# piezo_flasher_v2_0.net
KiCad netlist of a schematic drawn in EAGLE
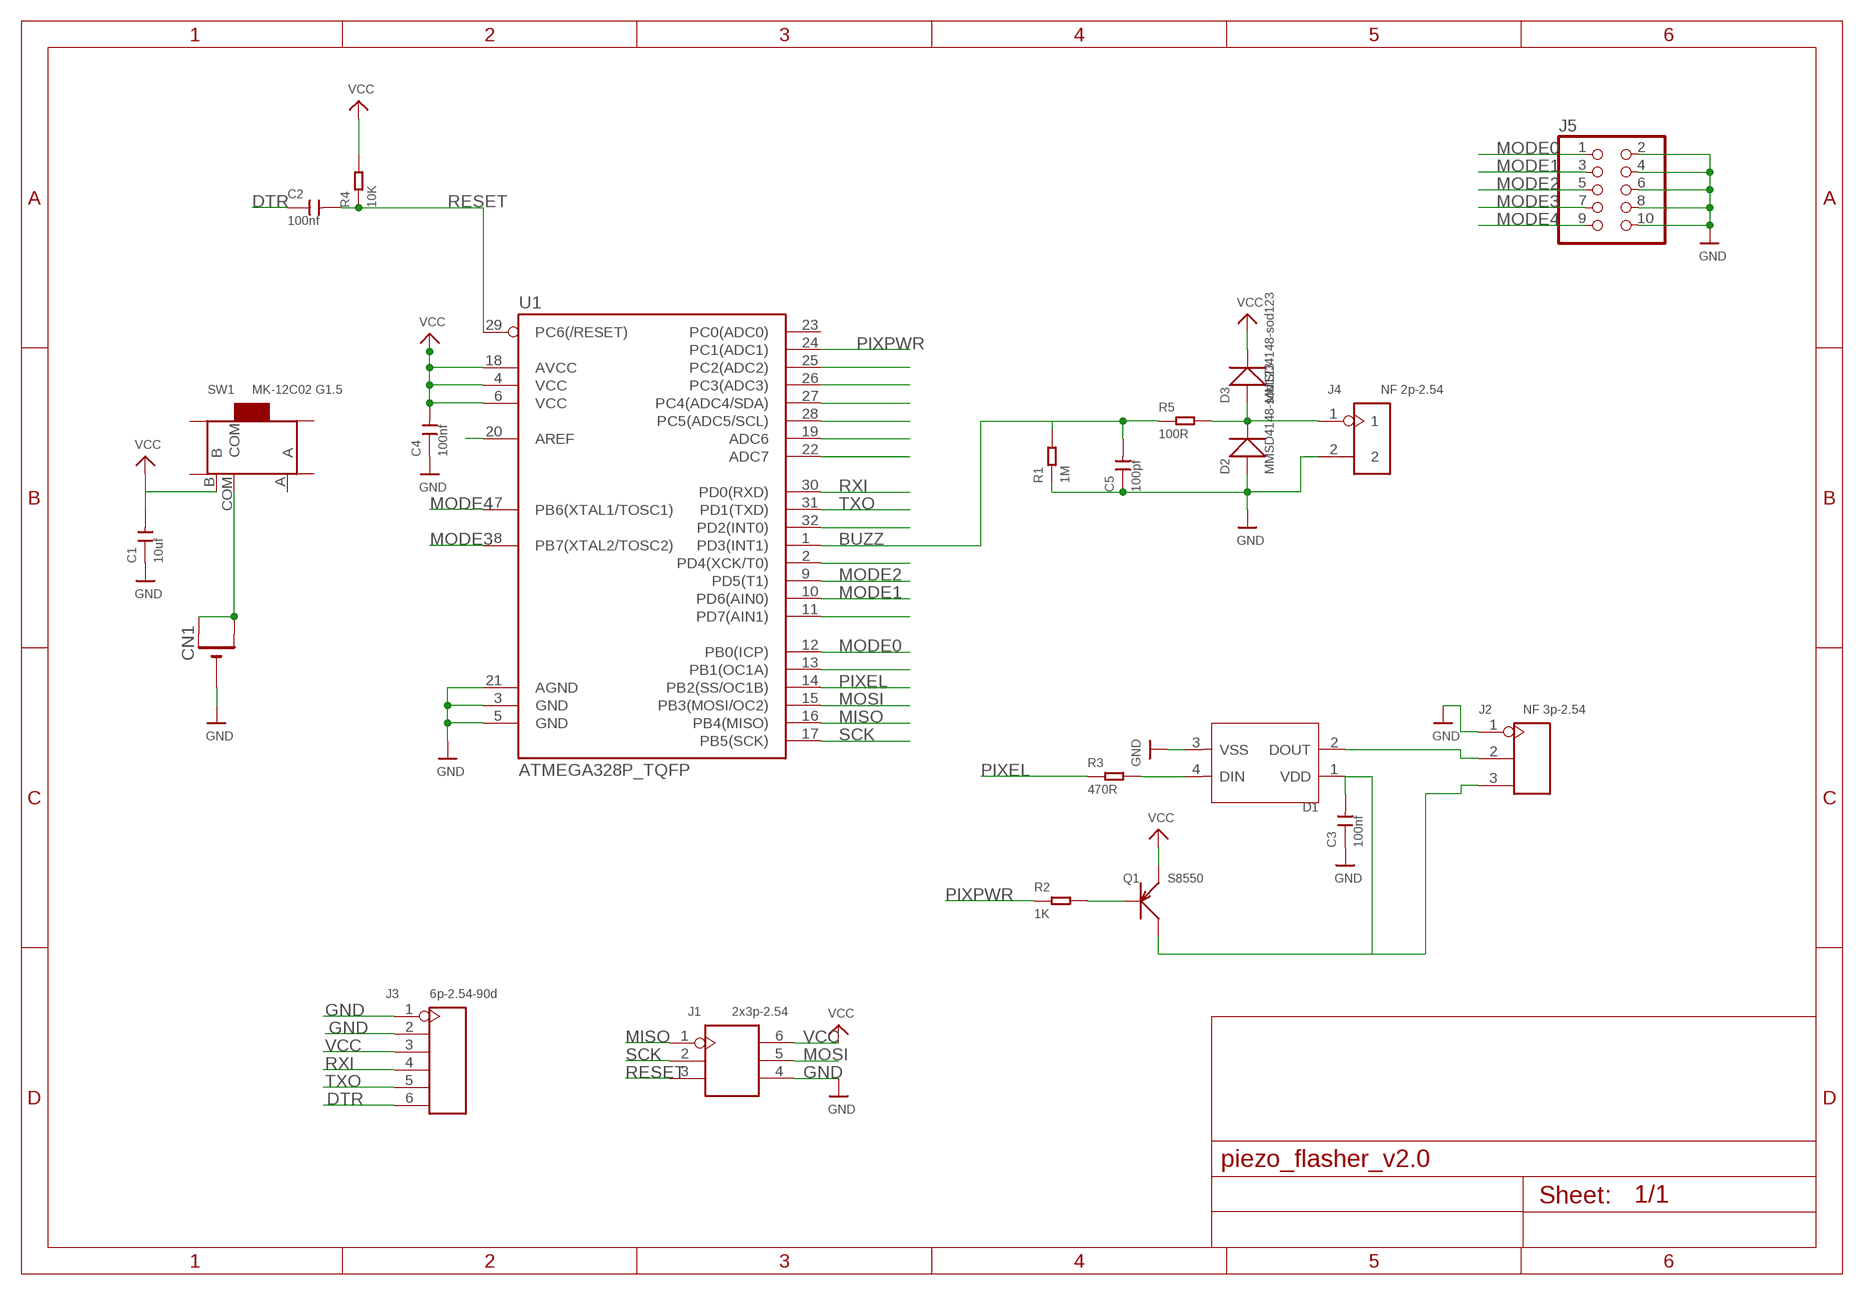
[diagram p0: schematic, sheet 1]

(export (version "E")
  (design (tool "Eeschema 10.0.6"))
  (components
    (comp (ref "C1")
      (value "10uf")
      (footprint "eagle-import:C0805")
      (fields (field (name "MPN") "CC0805KKX5R8BB106"))
      (libsource (lib "eagle-import") (part "CERAMIC-10UF-25V-10%-X5R(0805)"))
    )
    (comp (ref "C2")
      (value "100nf")
      (footprint "eagle-import:C0805")
      (fields (field (name "MPN") "CC0805KRX7R9BB104"))
      (libsource (lib "eagle-import") (part "CERAMIC-100NF-50V-10%-X7R(0805)"))
    )
    (comp (ref "C3")
      (value "100nf")
      (footprint "eagle-import:C0805")
      (fields (field (name "MPN") "CC0805KRX7R9BB104"))
      (libsource (lib "eagle-import") (part "CERAMIC-100NF-50V-10%-X7R(0805)"))
    )
    (comp (ref "C4")
      (value "100nf")
      (footprint "eagle-import:C0805")
      (fields (field (name "MPN") "CC0805KRX7R9BB104"))
      (libsource (lib "eagle-import") (part "CERAMIC-100NF-50V-10%-X7R(0805)"))
    )
    (comp (ref "C5")
      (value "100pf")
      (footprint "eagle-import:C0603")
      (fields (field (name "MPN") "CC0603JRNPO9BN101"))
      (libsource (lib "eagle-import") (part "CERAMIC-100PF-50V-5%-NPO(0603)"))
    )
    (comp (ref "CN1")
      (value "CR2032SMT")
      (footprint "eagle-import:CR2032-SMD")
      (libsource (lib "eagle-import") (part "CR2032SMT"))
    )
    (comp (ref "D1")
      (value "SMD-RGB-LED-4P'WS2812B'")
      (footprint "eagle-import:LED4-SMD-5050")
      (libsource (lib "eagle-import") (part "SMD-RGB-LED-4P'WS2812B'"))
    )
    (comp (ref "D2")
      (value "MMSD4148-sod123")
      (footprint "eagle-import:SOD-123")
      (fields (field (name "MPN") "MMSD4148"))
      (libsource (lib "eagle-import") (part "SMD-DIODE-100V-200MA(SOD-123)"))
    )
    (comp (ref "D3")
      (value "MMSD4148-sod123")
      (footprint "eagle-import:SOD-123")
      (fields (field (name "MPN") "MMSD4148"))
      (libsource (lib "eagle-import") (part "SMD-DIODE-100V-200MA(SOD-123)"))
    )
    (comp (ref "J1")
      (value "2x3p-2.54")
      (footprint "eagle-import:H2X3-2.54")
      (fields (field (name "MPN") "P125-12A1BS116A1"))
      (libsource (lib "eagle-import") (part "DIP-BLACK-MALE-HEADER(2X3P-2.54）-2.54"))
    )
    (comp (ref "J2")
      (value "NF 3p-2.54")
      (footprint "eagle-import:H3-2.54")
      (libsource (lib "eagle-import") (part "DIP-BLACK-MALE-HEADER-VERT(3P-2.54)"))
    )
    (comp (ref "J3")
      (value "6p-2.54-90d")
      (footprint "eagle-import:H6-2.54-90D-MALE")
      (libsource (lib "eagle-import") (part "DIP-BLACK-SHORT-MALE-HEADER-R/A(6P-2.54-90D)"))
    )
    (comp (ref "J4")
      (value "NF 2p-2.54")
      (footprint "eagle-import:H2-2.54")
      (fields (field (name "MPN") "P125-1102A0BS116A1"))
      (libsource (lib "eagle-import") (part "DIP-BLACK-MALE-HEADER-VERT(2P-2.54)"))
    )
    (comp (ref "J5")
      (value "HEADER-2X5")
      (footprint "eagle-import:2X05")
      (libsource (lib "eagle-import") (part "HEADER-2X5"))
    )
    (comp (ref "Q1")
      (value "S8550")
      (footprint "eagle-import:SOT-23")
      (libsource (lib "eagle-import") (part "SMD-TRANSISTORS-PNP-25V-500MA-S8550(SOT-23)"))
    )
    (comp (ref "R1")
      (value "1M")
      (footprint "eagle-import:R0603")
      (fields (field (name "MPN") "RC0603FR-071ML"))
      (libsource (lib "eagle-import") (part "SMD-RES-1M-1%-1/10W(0603)"))
    )
    (comp (ref "R2")
      (value "1K")
      (footprint "eagle-import:R0805")
      (fields (field (name "MPN") "RC0805JR-071KL"))
      (libsource (lib "eagle-import") (part "SMD-RES-1K-5%-1/8W(0805)"))
    )
    (comp (ref "R3")
      (value "470R")
      (footprint "eagle-import:R0603")
      (fields (field (name "MPN") "RC0603JR-07470RL"))
      (libsource (lib "eagle-import") (part "SMD-RES-470R-5%-1/10W(0603)"))
    )
    (comp (ref "R4")
      (value "10K")
      (footprint "eagle-import:R0805")
      (fields (field (name "MPN") "RC0805FR-0710KL"))
      (libsource (lib "eagle-import") (part "SMD-RES-10K-1%-1/8W(0805)"))
    )
    (comp (ref "R5")
      (value "100R")
      (footprint "eagle-import:R0805")
      (fields (field (name "MPN") "RC0805JR-07100RL"))
      (libsource (lib "eagle-import") (part "SMD-RES-100R-5%-1/8W(0805)"))
    )
    (comp (ref "SW1")
      (value "MK-12C02 G1.5")
      (footprint "eagle-import:SW7-SMD-L6.7X2.7X3.2MM")
      (libsource (lib "eagle-import") (part "SMD-TOGGLE-SWITCH-ON-ON(3+4P-6.7X2.7MM)"))
    )
    (comp (ref "U1")
      (value "ATMEGA328P_TQFP")
      (footprint "eagle-import:TQFP32-08")
      (libsource (lib "eagle-import") (part "ATMEGA328P_TQFP"))
    )
  )
  (nets
    (net (code "1") (name "/BUZZ") (class "Default")
      (node (ref "C5") (pin "2") (pinfunction "2_2") (pintype "passive"))
      (node (ref "R1") (pin "2") (pinfunction "2_2") (pintype "passive"))
      (node (ref "R5") (pin "1") (pinfunction "1_1") (pintype "passive"))
      (node (ref "U1") (pin "1") (pinfunction "PD3(INT1)_1") (pintype "bidirectional"))
    )
    (net (code "2") (name "/DTR") (class "Default")
      (node (ref "C2") (pin "1") (pinfunction "1_1") (pintype "passive"))
      (node (ref "J3") (pin "6") (pinfunction "6_6") (pintype "bidirectional"))
    )
    (net (code "3") (name "/MISO") (class "Default")
      (node (ref "J1") (pin "1") (pinfunction "1_1") (pintype "bidirectional"))
      (node (ref "U1") (pin "16") (pinfunction "PB4(MISO)_16") (pintype "bidirectional"))
    )
    (net (code "4") (name "/MODE0") (class "Default")
      (node (ref "J5") (pin "1") (pinfunction "1_1") (pintype "passive"))
      (node (ref "U1") (pin "12") (pinfunction "PB0(ICP)_12") (pintype "bidirectional"))
    )
    (net (code "5") (name "/MODE1") (class "Default")
      (node (ref "J5") (pin "3") (pinfunction "3_3") (pintype "passive"))
      (node (ref "U1") (pin "10") (pinfunction "PD6(AIN0)_10") (pintype "bidirectional"))
    )
    (net (code "6") (name "/MODE2") (class "Default")
      (node (ref "J5") (pin "5") (pinfunction "5_5") (pintype "passive"))
      (node (ref "U1") (pin "9") (pinfunction "PD5(T1)_9") (pintype "bidirectional"))
    )
    (net (code "7") (name "/MODE3") (class "Default")
      (node (ref "J5") (pin "7") (pinfunction "7_7") (pintype "passive"))
      (node (ref "U1") (pin "8") (pinfunction "PB7(XTAL2/TOSC2)_8") (pintype "bidirectional"))
    )
    (net (code "8") (name "/MODE4") (class "Default")
      (node (ref "J5") (pin "9") (pinfunction "9_9") (pintype "passive"))
      (node (ref "U1") (pin "7") (pinfunction "PB6(XTAL1/TOSC1)_7") (pintype "bidirectional"))
    )
    (net (code "9") (name "/MOSI") (class "Default")
      (node (ref "J1") (pin "5") (pinfunction "5_5") (pintype "bidirectional"))
      (node (ref "U1") (pin "15") (pinfunction "PB3(MOSI/OC2)_15") (pintype "bidirectional"))
    )
    (net (code "10") (name "/PIXEL") (class "Default")
      (node (ref "R3") (pin "1") (pinfunction "1_1") (pintype "passive"))
      (node (ref "U1") (pin "14") (pinfunction "PB2(SS/OC1B)_14") (pintype "bidirectional"))
    )
    (net (code "11") (name "/PIXPWR") (class "Default")
      (node (ref "R2") (pin "1") (pinfunction "1_1") (pintype "passive"))
      (node (ref "U1") (pin "24") (pinfunction "PC1(ADC1)_24") (pintype "bidirectional"))
    )
    (net (code "12") (name "/RESET") (class "Default")
      (node (ref "C2") (pin "2") (pinfunction "2_2") (pintype "passive"))
      (node (ref "J1") (pin "3") (pinfunction "3_3") (pintype "bidirectional"))
      (node (ref "R4") (pin "1") (pinfunction "1_1") (pintype "passive"))
      (node (ref "U1") (pin "29") (pinfunction "PC6(/RESET)_29") (pintype "bidirectional"))
    )
    (net (code "13") (name "/RXI") (class "Default")
      (node (ref "J3") (pin "4") (pinfunction "4_4") (pintype "bidirectional"))
      (node (ref "U1") (pin "30") (pinfunction "PD0(RXD)_30") (pintype "bidirectional"))
    )
    (net (code "14") (name "/SCK") (class "Default")
      (node (ref "J1") (pin "2") (pinfunction "2_2") (pintype "bidirectional"))
      (node (ref "U1") (pin "17") (pinfunction "PB5(SCK)_17") (pintype "bidirectional"))
    )
    (net (code "15") (name "/TXO") (class "Default")
      (node (ref "J3") (pin "5") (pinfunction "5_5") (pintype "bidirectional"))
      (node (ref "U1") (pin "31") (pinfunction "PD1(TXD)_31") (pintype "bidirectional"))
    )
    (net (code "16") (name "GND") (class "Default")
      (node (ref "C1") (pin "1") (pinfunction "1_1") (pintype "passive"))
      (node (ref "C3") (pin "1") (pinfunction "1_1") (pintype "passive"))
      (node (ref "C4") (pin "1") (pinfunction "1_1") (pintype "passive"))
      (node (ref "C5") (pin "1") (pinfunction "1_1") (pintype "passive"))
      (node (ref "CN1") (pin "-") (pinfunction "-_-") (pintype "passive"))
      (node (ref "D1") (pin "3") (pinfunction "VSS_3") (pintype "bidirectional"))
      (node (ref "D2") (pin "+") (pinfunction "+_+") (pintype "passive"))
      (node (ref "J1") (pin "4") (pinfunction "4_4") (pintype "bidirectional"))
      (node (ref "J2") (pin "1") (pinfunction "P$1_1") (pintype "bidirectional"))
      (node (ref "J3") (pin "1") (pinfunction "1_1") (pintype "bidirectional"))
      (node (ref "J3") (pin "2") (pinfunction "2_2") (pintype "bidirectional"))
      (node (ref "J4") (pin "2") (pinfunction "2_2") (pintype "bidirectional"))
      (node (ref "J5") (pin "10") (pinfunction "10_10") (pintype "passive"))
      (node (ref "J5") (pin "2") (pinfunction "2_2") (pintype "passive"))
      (node (ref "J5") (pin "4") (pinfunction "4_4") (pintype "passive"))
      (node (ref "J5") (pin "6") (pinfunction "6_6") (pintype "passive"))
      (node (ref "J5") (pin "8") (pinfunction "8_8") (pintype "passive"))
      (node (ref "R1") (pin "1") (pinfunction "1_1") (pintype "passive"))
      (node (ref "U1") (pin "21") (pinfunction "AGND_21") (pintype "bidirectional"))
      (node (ref "U1") (pin "3") (pinfunction "GND_3") (pintype "bidirectional"))
      (node (ref "U1") (pin "5") (pinfunction "GND_5") (pintype "bidirectional"))
    )
    (net (code "17") (name "Net-(CN1-+)") (class "Default")
      (node (ref "CN1") (pin "+$1") (pinfunction "+_+$1") (pintype "passive"))
      (node (ref "CN1") (pin "+$2") (pinfunction "+1_+$2") (pintype "passive"))
      (node (ref "SW1") (pin "COM") (pinfunction "COM_COM") (pintype "bidirectional"))
    )
    (net (code "18") (name "Net-(D1-DIN)") (class "Default")
      (node (ref "D1") (pin "4") (pinfunction "DIN_4") (pintype "bidirectional"))
      (node (ref "R3") (pin "2") (pinfunction "2_2") (pintype "passive"))
    )
    (net (code "19") (name "Net-(D1-DOUT)") (class "Default")
      (node (ref "D1") (pin "2") (pinfunction "DOUT_2") (pintype "bidirectional"))
      (node (ref "J2") (pin "2") (pinfunction "P$2_2") (pintype "bidirectional"))
    )
    (net (code "20") (name "Net-(D1-VDD)") (class "Default")
      (node (ref "C3") (pin "2") (pinfunction "2_2") (pintype "passive"))
      (node (ref "D1") (pin "1") (pinfunction "VDD_1") (pintype "bidirectional"))
      (node (ref "J2") (pin "3") (pinfunction "P$3_3") (pintype "bidirectional"))
      (node (ref "Q1") (pin "3") (pinfunction "C_3") (pintype "passive"))
    )
    (net (code "21") (name "Net-(D2-Pad-)") (class "Default")
      (node (ref "D2") (pin "-") (pinfunction "-_-") (pintype "passive"))
      (node (ref "D3") (pin "+") (pinfunction "+_+") (pintype "passive"))
      (node (ref "J4") (pin "1") (pinfunction "1_1") (pintype "bidirectional"))
      (node (ref "R5") (pin "2") (pinfunction "2_2") (pintype "passive"))
    )
    (net (code "22") (name "Net-(Q1-B)") (class "Default")
      (node (ref "Q1") (pin "1") (pinfunction "B_1") (pintype "passive"))
      (node (ref "R2") (pin "2") (pinfunction "2_2") (pintype "passive"))
    )
    (net (code "23") (name "VCC") (class "Default")
      (node (ref "C1") (pin "2") (pinfunction "2_2") (pintype "passive"))
      (node (ref "C4") (pin "2") (pinfunction "2_2") (pintype "passive"))
      (node (ref "D3") (pin "-") (pinfunction "-_-") (pintype "passive"))
      (node (ref "J1") (pin "6") (pinfunction "6_6") (pintype "bidirectional"))
      (node (ref "J3") (pin "3") (pinfunction "3_3") (pintype "bidirectional"))
      (node (ref "Q1") (pin "2") (pinfunction "E_2") (pintype "passive"))
      (node (ref "R4") (pin "2") (pinfunction "2_2") (pintype "passive"))
      (node (ref "SW1") (pin "B") (pinfunction "B_B") (pintype "bidirectional"))
      (node (ref "U1") (pin "18") (pinfunction "AVCC_18") (pintype "bidirectional"))
      (node (ref "U1") (pin "4") (pinfunction "VCC_4") (pintype "bidirectional"))
      (node (ref "U1") (pin "6") (pinfunction "VCC_6") (pintype "bidirectional"))
    )
    (net (code "24") (name "unconnected-(SW1-PadA)") (class "Default")
      (node (ref "SW1") (pin "A") (pinfunction "A_A") (pintype "bidirectional"))
    )
    (net (code "25") (name "unconnected-(SW1-PadSS1)") (class "Default")
      (node (ref "SW1") (pin "SS1") (pinfunction "SS1_SS1") (pintype "bidirectional"))
    )
    (net (code "26") (name "unconnected-(SW1-PadSS2)") (class "Default")
      (node (ref "SW1") (pin "SS2") (pinfunction "SS2_SS2") (pintype "bidirectional"))
    )
    (net (code "27") (name "unconnected-(SW1-PadSS3)") (class "Default")
      (node (ref "SW1") (pin "SS3") (pinfunction "SS3_SS3") (pintype "bidirectional"))
    )
    (net (code "28") (name "unconnected-(SW1-PadSS4)") (class "Default")
      (node (ref "SW1") (pin "SS4") (pinfunction "SS4_SS4") (pintype "bidirectional"))
    )
    (net (code "29") (name "unconnected-(U1-ADC6-Pad19)") (class "Default")
      (node (ref "U1") (pin "19") (pinfunction "ADC6_19") (pintype "bidirectional"))
    )
    (net (code "30") (name "unconnected-(U1-ADC7-Pad22)") (class "Default")
      (node (ref "U1") (pin "22") (pinfunction "ADC7_22") (pintype "bidirectional"))
    )
    (net (code "31") (name "unconnected-(U1-AREF-Pad20)") (class "Default")
      (node (ref "U1") (pin "20") (pinfunction "AREF_20") (pintype "bidirectional"))
    )
    (net (code "32") (name "unconnected-(U1-PB1(OC1A)-Pad13)") (class "Default")
      (node (ref "U1") (pin "13") (pinfunction "PB1(OC1A)_13") (pintype "bidirectional"))
    )
    (net (code "33") (name "unconnected-(U1-PC0(ADC0)-Pad23)") (class "Default")
      (node (ref "U1") (pin "23") (pinfunction "PC0(ADC0)_23") (pintype "bidirectional"))
    )
    (net (code "34") (name "unconnected-(U1-PC2(ADC2)-Pad25)") (class "Default")
      (node (ref "U1") (pin "25") (pinfunction "PC2(ADC2)_25") (pintype "bidirectional"))
    )
    (net (code "35") (name "unconnected-(U1-PC3(ADC3)-Pad26)") (class "Default")
      (node (ref "U1") (pin "26") (pinfunction "PC3(ADC3)_26") (pintype "bidirectional"))
    )
    (net (code "36") (name "unconnected-(U1-PC4(ADC4{slash}SDA)-Pad27)") (class "Default")
      (node (ref "U1") (pin "27") (pinfunction "PC4(ADC4/SDA)_27") (pintype "bidirectional"))
    )
    (net (code "37") (name "unconnected-(U1-PC5(ADC5{slash}SCL)-Pad28)") (class "Default")
      (node (ref "U1") (pin "28") (pinfunction "PC5(ADC5/SCL)_28") (pintype "bidirectional"))
    )
    (net (code "38") (name "unconnected-(U1-PD2(INT0)-Pad32)") (class "Default")
      (node (ref "U1") (pin "32") (pinfunction "PD2(INT0)_32") (pintype "bidirectional"))
    )
    (net (code "39") (name "unconnected-(U1-PD4(XCK{slash}T0)-Pad2)") (class "Default")
      (node (ref "U1") (pin "2") (pinfunction "PD4(XCK/T0)_2") (pintype "bidirectional"))
    )
    (net (code "40") (name "unconnected-(U1-PD7(AIN1)-Pad11)") (class "Default")
      (node (ref "U1") (pin "11") (pinfunction "PD7(AIN1)_11") (pintype "bidirectional"))
    )
  )
)
